# IO_Combo_WiFi.net
KiCad netlist of a schematic drawn in Altium Designer
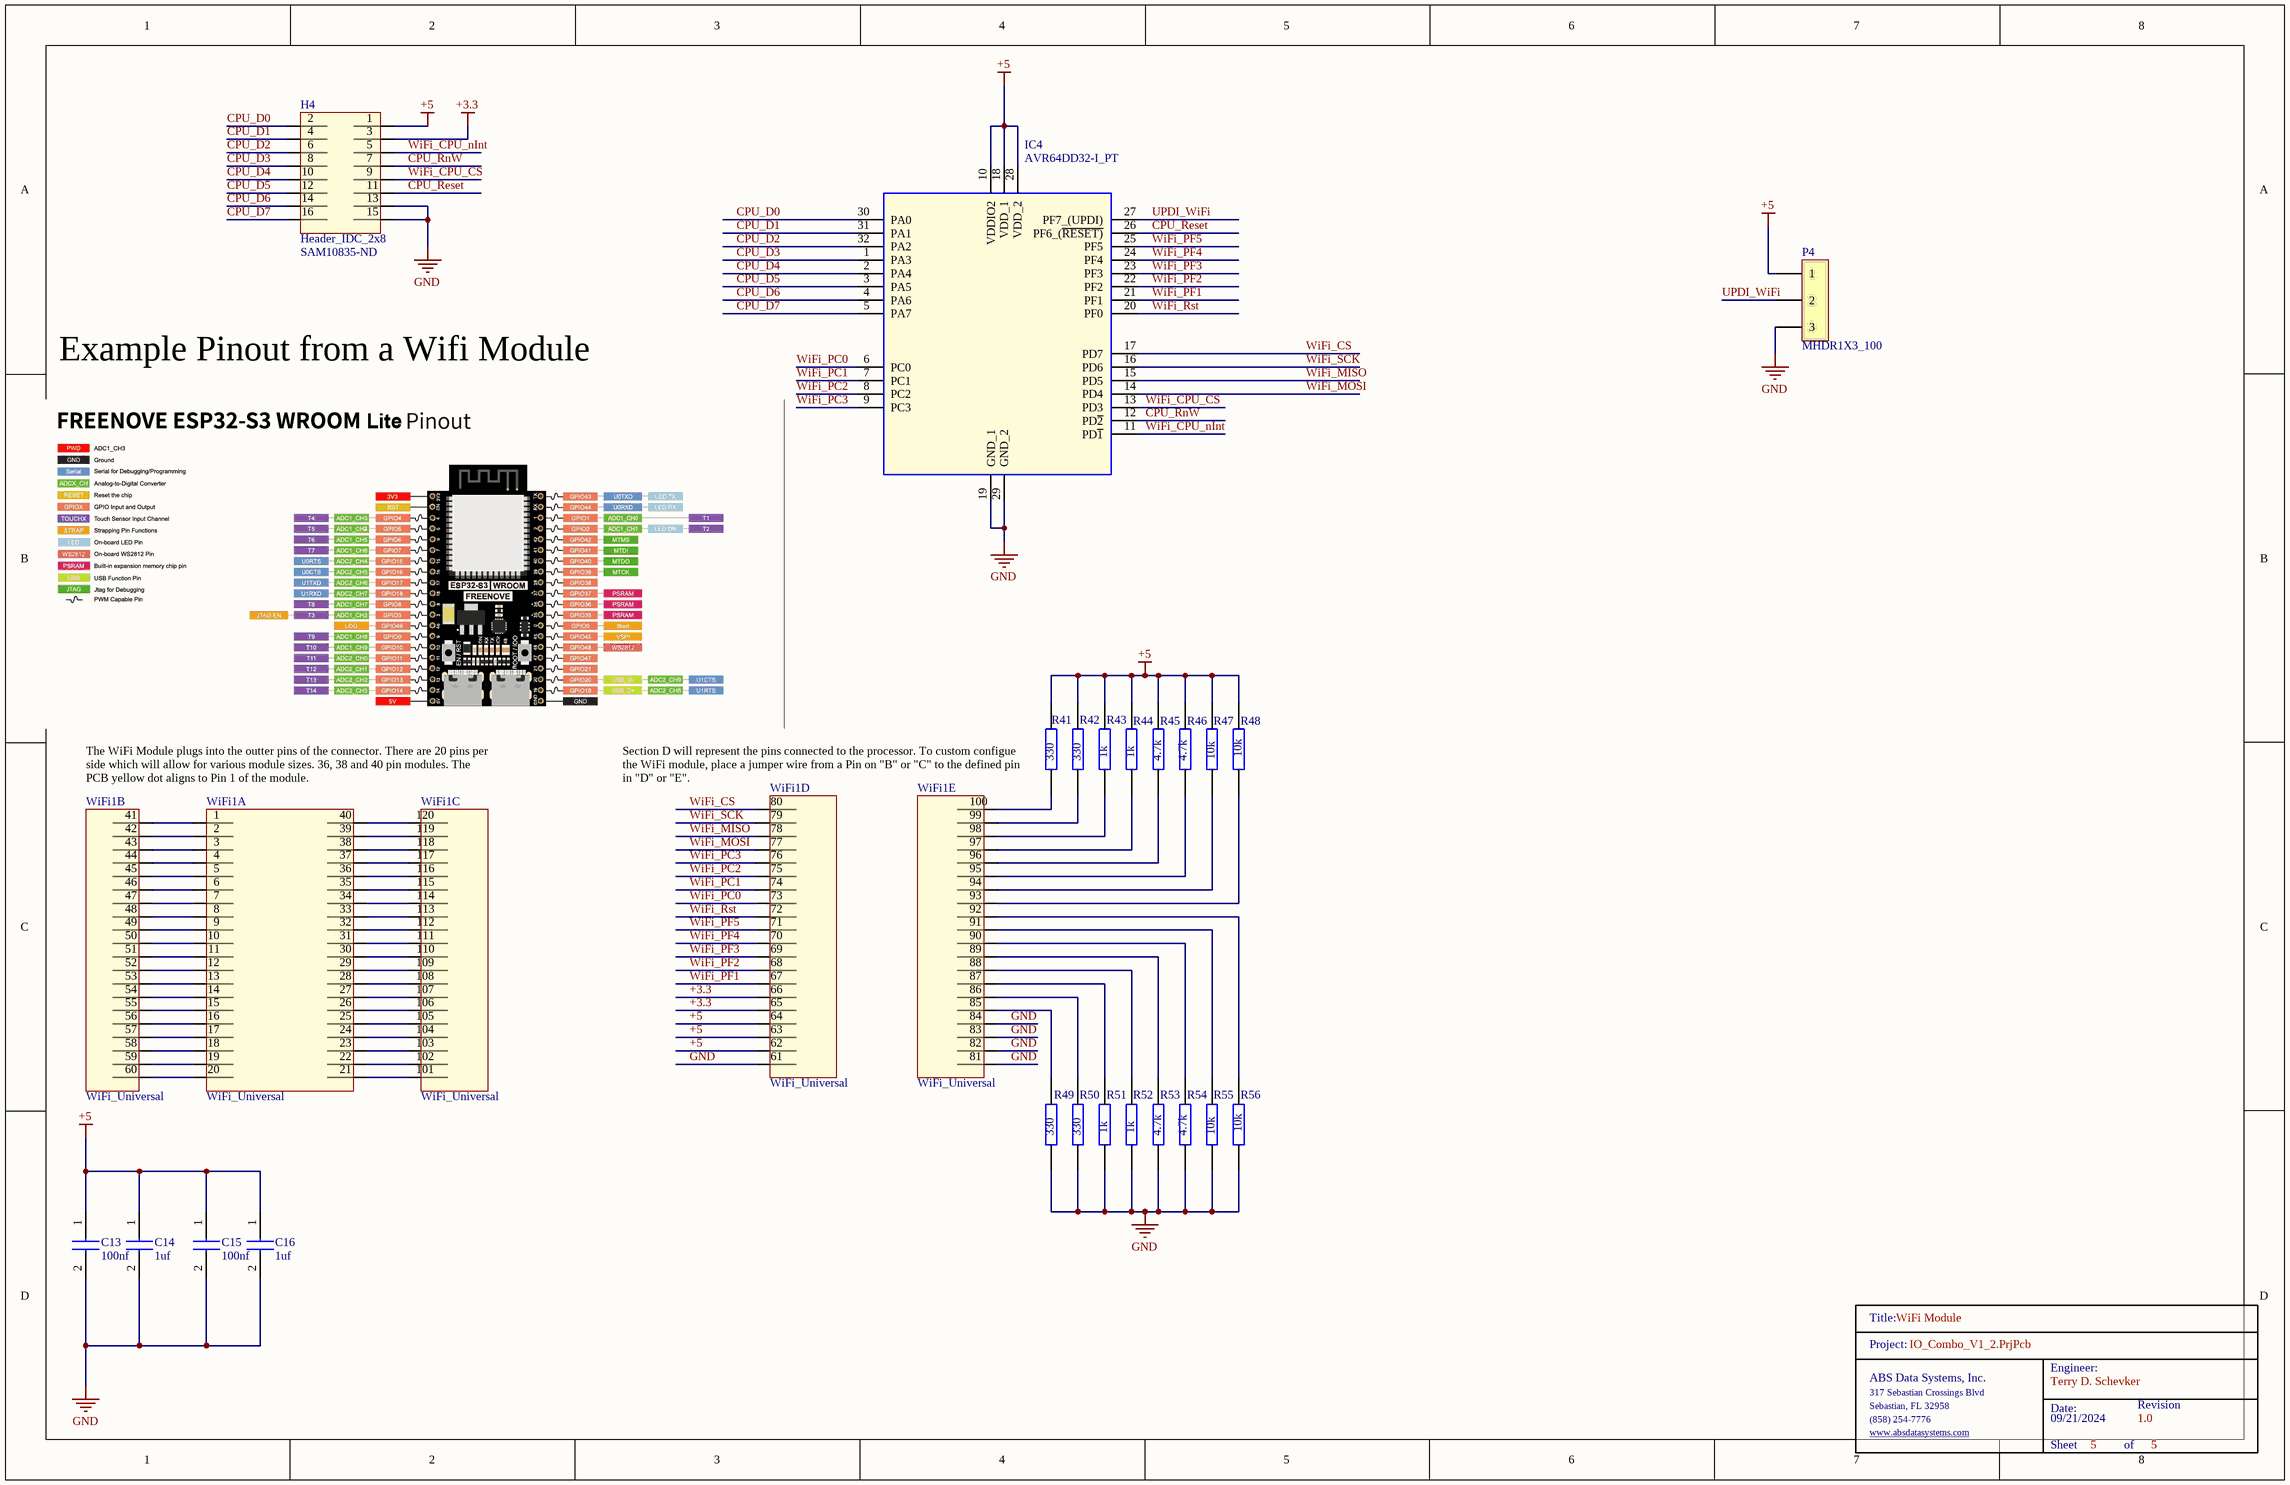
[diagram p0: IO_Combo_WiFi.SchDoc]

(export (version "E")
  (design (tool "Eeschema 10.0.6"))
  (components
    (comp (ref "C13")
      (value "100nf")
      (footprint "0603")
      (description "Samsung Electro-Mechanics 0603 100nf")
      (libsource (lib "Capacitors") (part "CL10B104JB8NNNC"))
    )
    (comp (ref "C14")
      (value "1uf")
      (footprint "0603")
      (description "Samsung Electro-Mechanics 0603 1uf")
      (libsource (lib "Capacitors") (part "CL10B105KA8NNNL"))
    )
    (comp (ref "C15")
      (value "100nf")
      (footprint "0603")
      (description "Samsung Electro-Mechanics 0603 100nf")
      (libsource (lib "Capacitors") (part "CL10B104JB8NNNC"))
    )
    (comp (ref "C16")
      (value "1uf")
      (footprint "0603")
      (description "Samsung Electro-Mechanics 0603 1uf")
      (libsource (lib "Capacitors") (part "CL10B105KA8NNNL"))
    )
    (comp (ref "H4")
      (value "Header_IDC_2x8")
      (footprint "HEADER16")
      (description "16 Pin 2x8 Through Hold IDC Connector")
      (fields
        (field (name "MANUFACTURER") "Samtec")
        (field (name "MANUFACTURER PART NUMBER") "TST-108-01-G-D")
        (field (name "SUPPLIER PART NUMBER 1") "SAM10835-ND")
      )
      (libsource (lib "Misc") (part "Header_IDC_2x8"))
    )
    (comp (ref "IC4")
      (value "AVR64DD32-I_PT")
      (footprint "CPU_Memory:QFP80P900X900X120-32N")
      (description "Integrated Circuit")
      (fields (field (name "MANUFACTURER_PART_NUMBER") "AVR64DD32-I/PT ¦ MULTI-VOLTAGE I/O"))
      (libsource (lib "CPU_Memory") (part "AVR64DD32-I_PT"))
    )
    (comp (ref "P4")
      (value "MHDR1X3_100")
      (footprint "MHDR1X3_100")
      (description "Header, 3-Pin")
      (fields (field (name "PUBLISHER") "Altium Limited"))
      (libsource (lib "Connectors") (part "MHDR1X3_100"))
    )
    (comp (ref "R41")
      (value "330")
      (footprint "0603")
      (description "YAGEO 0603 330 ohm")
      (fields
        (field (name "MOUSER PART NUMBER") "603-RC0603JR-070RL")
        (field (name "MANUFACTURER_PART_NUMBER") "RC0603JR-070RL")
      )
      (libsource (lib "Resistors") (part "AC0603FR-10330RL"))
    )
    (comp (ref "R42")
      (value "330")
      (footprint "0603")
      (description "YAGEO 0603 330 ohm")
      (fields
        (field (name "MOUSER PART NUMBER") "603-RC0603JR-070RL")
        (field (name "MANUFACTURER_PART_NUMBER") "RC0603JR-070RL")
      )
      (libsource (lib "Resistors") (part "AC0603FR-10330RL"))
    )
    (comp (ref "R43")
      (value "1k")
      (footprint "0603")
      (description "YAGEO 0603 1k ohm")
      (fields
        (field (name "MOUSER PART NUMBER") "603-RC0603JR-070RL")
        (field (name "MANUFACTURER_PART_NUMBER") "RC0603JR-070RL")
      )
      (libsource (lib "Resistors") (part "AC0603FR-7W1KL_1"))
    )
    (comp (ref "R44")
      (value "1k")
      (footprint "0603")
      (description "YAGEO 0603 1k ohm")
      (fields
        (field (name "MOUSER PART NUMBER") "603-RC0603JR-070RL")
        (field (name "MANUFACTURER_PART_NUMBER") "RC0603JR-070RL")
      )
      (libsource (lib "Resistors") (part "AC0603FR-7W1KL_1"))
    )
    (comp (ref "R45")
      (value "4.7k")
      (footprint "0603")
      (description "YAGEO 0603 4.7k")
      (fields
        (field (name "MOUSER PART NUMBER") "603-RC0603JR-070RL")
        (field (name "MANUFACTURER_PART_NUMBER") "RC0603JR-070RL")
      )
      (libsource (lib "Resistors") (part "RC0603FR-104K7L"))
    )
    (comp (ref "R46")
      (value "4.7k")
      (footprint "0603")
      (description "YAGEO 0603 4.7k")
      (fields
        (field (name "MOUSER PART NUMBER") "603-RC0603JR-070RL")
        (field (name "MANUFACTURER_PART_NUMBER") "RC0603JR-070RL")
      )
      (libsource (lib "Resistors") (part "RC0603FR-104K7L"))
    )
    (comp (ref "R47")
      (value "10k")
      (footprint "0603")
      (description "YAGEO 0603 10k ohm")
      (fields
        (field (name "MOUSER PART NUMBER") "603-RC0603JR-070RL")
        (field (name "MANUFACTURER_PART_NUMBER") "RC0603JR-070RL")
      )
      (libsource (lib "Resistors") (part "RC0603JR-0710KL"))
    )
    (comp (ref "R48")
      (value "10k")
      (footprint "0603")
      (description "YAGEO 0603 10k ohm")
      (fields
        (field (name "MOUSER PART NUMBER") "603-RC0603JR-070RL")
        (field (name "MANUFACTURER_PART_NUMBER") "RC0603JR-070RL")
      )
      (libsource (lib "Resistors") (part "RC0603JR-0710KL"))
    )
    (comp (ref "R49")
      (value "330")
      (footprint "0603")
      (description "YAGEO 0603 330 ohm")
      (fields
        (field (name "MOUSER PART NUMBER") "603-RC0603JR-070RL")
        (field (name "MANUFACTURER_PART_NUMBER") "RC0603JR-070RL")
      )
      (libsource (lib "Resistors") (part "AC0603FR-10330RL"))
    )
    (comp (ref "R50")
      (value "330")
      (footprint "0603")
      (description "YAGEO 0603 330 ohm")
      (fields
        (field (name "MOUSER PART NUMBER") "603-RC0603JR-070RL")
        (field (name "MANUFACTURER_PART_NUMBER") "RC0603JR-070RL")
      )
      (libsource (lib "Resistors") (part "AC0603FR-10330RL"))
    )
    (comp (ref "R51")
      (value "1k")
      (footprint "0603")
      (description "YAGEO 0603 1k ohm")
      (fields
        (field (name "MOUSER PART NUMBER") "603-RC0603JR-070RL")
        (field (name "MANUFACTURER_PART_NUMBER") "RC0603JR-070RL")
      )
      (libsource (lib "Resistors") (part "AC0603FR-7W1KL_1"))
    )
    (comp (ref "R52")
      (value "1k")
      (footprint "0603")
      (description "YAGEO 0603 1k ohm")
      (fields
        (field (name "MOUSER PART NUMBER") "603-RC0603JR-070RL")
        (field (name "MANUFACTURER_PART_NUMBER") "RC0603JR-070RL")
      )
      (libsource (lib "Resistors") (part "AC0603FR-7W1KL_1"))
    )
    (comp (ref "R53")
      (value "4.7k")
      (footprint "0603")
      (description "YAGEO 0603 4.7k")
      (fields
        (field (name "MOUSER PART NUMBER") "603-RC0603JR-070RL")
        (field (name "MANUFACTURER_PART_NUMBER") "RC0603JR-070RL")
      )
      (libsource (lib "Resistors") (part "RC0603FR-104K7L"))
    )
    (comp (ref "R54")
      (value "4.7k")
      (footprint "0603")
      (description "YAGEO 0603 4.7k")
      (fields
        (field (name "MOUSER PART NUMBER") "603-RC0603JR-070RL")
        (field (name "MANUFACTURER_PART_NUMBER") "RC0603JR-070RL")
      )
      (libsource (lib "Resistors") (part "RC0603FR-104K7L"))
    )
    (comp (ref "R55")
      (value "10k")
      (footprint "0603")
      (description "YAGEO 0603 10k ohm")
      (fields
        (field (name "MOUSER PART NUMBER") "603-RC0603JR-070RL")
        (field (name "MANUFACTURER_PART_NUMBER") "RC0603JR-070RL")
      )
      (libsource (lib "Resistors") (part "RC0603JR-0710KL"))
    )
    (comp (ref "R56")
      (value "10k")
      (footprint "0603")
      (description "YAGEO 0603 10k ohm")
      (fields
        (field (name "MOUSER PART NUMBER") "603-RC0603JR-070RL")
        (field (name "MANUFACTURER_PART_NUMBER") "RC0603JR-070RL")
      )
      (libsource (lib "Resistors") (part "RC0603JR-0710KL"))
    )
    (comp (ref "WiFi1")
      (value "WiFi_Universal")
      (footprint "WiFI_Universal")
      (libsource (lib "Misc") (part "WiFi_Universal"))
    )
  )
  (nets
    (net (code "1") (name "+3.3") (class "Default")
      (node (ref "H4") (pin "3") (pinfunction "3_3") (pintype "passive"))
      (node (ref "WiFi1") (pin "65") (pinfunction "65_65") (pintype "passive"))
      (node (ref "WiFi1") (pin "66") (pinfunction "66_66") (pintype "passive"))
    )
    (net (code "2") (name "+5") (class "Default")
      (node (ref "C13") (pin "1") (pinfunction "1_1") (pintype "passive"))
      (node (ref "C14") (pin "1") (pinfunction "1_1") (pintype "passive"))
      (node (ref "C15") (pin "1") (pinfunction "1_1") (pintype "passive"))
      (node (ref "C16") (pin "1") (pinfunction "1_1") (pintype "passive"))
      (node (ref "H4") (pin "1") (pinfunction "1_1") (pintype "passive"))
      (node (ref "IC4") (pin "10") (pinfunction "VDDIO2_10") (pintype "passive"))
      (node (ref "IC4") (pin "18") (pinfunction "VDD_1_18") (pintype "passive"))
      (node (ref "IC4") (pin "28") (pinfunction "VDD_2_28") (pintype "passive"))
      (node (ref "P4") (pin "1") (pinfunction "1_1") (pintype "passive"))
      (node (ref "R41") (pin "1") (pinfunction "1_1") (pintype "passive"))
      (node (ref "R42") (pin "1") (pinfunction "1_1") (pintype "passive"))
      (node (ref "R43") (pin "1") (pinfunction "1_1") (pintype "passive"))
      (node (ref "R44") (pin "1") (pinfunction "1_1") (pintype "passive"))
      (node (ref "R45") (pin "1") (pinfunction "1_1") (pintype "passive"))
      (node (ref "R46") (pin "1") (pinfunction "1_1") (pintype "passive"))
      (node (ref "R47") (pin "1") (pinfunction "1_1") (pintype "passive"))
      (node (ref "R48") (pin "1") (pinfunction "1_1") (pintype "passive"))
      (node (ref "WiFi1") (pin "62") (pinfunction "62_62") (pintype "passive"))
      (node (ref "WiFi1") (pin "63") (pinfunction "63_63") (pintype "passive"))
      (node (ref "WiFi1") (pin "64") (pinfunction "64_64") (pintype "passive"))
    )
    (net (code "3") (name "/CPU_D0") (class "Default")
      (node (ref "H4") (pin "2") (pinfunction "2_2") (pintype "passive"))
      (node (ref "IC4") (pin "30") (pinfunction "PA0_30") (pintype "passive"))
    )
    (net (code "4") (name "/CPU_D1") (class "Default")
      (node (ref "H4") (pin "4") (pinfunction "4_4") (pintype "passive"))
      (node (ref "IC4") (pin "31") (pinfunction "PA1_31") (pintype "passive"))
    )
    (net (code "5") (name "/CPU_D2") (class "Default")
      (node (ref "H4") (pin "6") (pinfunction "6_6") (pintype "passive"))
      (node (ref "IC4") (pin "32") (pinfunction "PA2_32") (pintype "passive"))
    )
    (net (code "6") (name "/CPU_D3") (class "Default")
      (node (ref "H4") (pin "8") (pinfunction "8_8") (pintype "passive"))
      (node (ref "IC4") (pin "1") (pinfunction "PA3_1") (pintype "passive"))
    )
    (net (code "7") (name "/CPU_D4") (class "Default")
      (node (ref "H4") (pin "10") (pinfunction "10_10") (pintype "passive"))
      (node (ref "IC4") (pin "2") (pinfunction "PA4_2") (pintype "passive"))
    )
    (net (code "8") (name "/CPU_D5") (class "Default")
      (node (ref "H4") (pin "12") (pinfunction "12_12") (pintype "passive"))
      (node (ref "IC4") (pin "3") (pinfunction "PA5_3") (pintype "passive"))
    )
    (net (code "9") (name "/CPU_D6") (class "Default")
      (node (ref "H4") (pin "14") (pinfunction "14_14") (pintype "passive"))
      (node (ref "IC4") (pin "4") (pinfunction "PA6_4") (pintype "passive"))
    )
    (net (code "10") (name "/CPU_D7") (class "Default")
      (node (ref "H4") (pin "16") (pinfunction "16_16") (pintype "passive"))
      (node (ref "IC4") (pin "5") (pinfunction "PA7_5") (pintype "passive"))
    )
    (net (code "11") (name "/CPU_Reset") (class "Default")
      (node (ref "H4") (pin "11") (pinfunction "11_11") (pintype "passive"))
      (node (ref "IC4") (pin "26") (pinfunction "PF6_(~{RESET)}_26") (pintype "passive"))
    )
    (net (code "12") (name "/CPU_RnW") (class "Default")
      (node (ref "H4") (pin "7") (pinfunction "7_7") (pintype "passive"))
      (node (ref "IC4") (pin "12") (pinfunction "PD~{2}_12") (pintype "passive"))
    )
    (net (code "13") (name "/UPDI_WiFi") (class "Default")
      (node (ref "IC4") (pin "27") (pinfunction "PF7_(UPDI)_27") (pintype "passive"))
      (node (ref "P4") (pin "2") (pinfunction "2_2") (pintype "passive"))
    )
    (net (code "14") (name "/WiFi_CPU_CS") (class "Default")
      (node (ref "H4") (pin "9") (pinfunction "9_9") (pintype "passive"))
      (node (ref "IC4") (pin "13") (pinfunction "PD3_13") (pintype "passive"))
    )
    (net (code "15") (name "/WiFi_CPU_nInt") (class "Default")
      (node (ref "H4") (pin "5") (pinfunction "5_5") (pintype "passive"))
      (node (ref "IC4") (pin "11") (pinfunction "PD~{1}_11") (pintype "passive"))
    )
    (net (code "16") (name "/WiFi_CS") (class "Default")
      (node (ref "IC4") (pin "17") (pinfunction "PD7_17") (pintype "passive"))
      (node (ref "WiFi1") (pin "80") (pinfunction "80_80") (pintype "passive"))
    )
    (net (code "17") (name "/WiFi_MISO") (class "Default")
      (node (ref "IC4") (pin "15") (pinfunction "PD5_15") (pintype "passive"))
      (node (ref "WiFi1") (pin "78") (pinfunction "78_78") (pintype "passive"))
    )
    (net (code "18") (name "/WiFi_MOSI") (class "Default")
      (node (ref "IC4") (pin "14") (pinfunction "PD4_14") (pintype "passive"))
      (node (ref "WiFi1") (pin "77") (pinfunction "77_77") (pintype "passive"))
    )
    (net (code "19") (name "/WiFi_PC0") (class "Default")
      (node (ref "IC4") (pin "6") (pinfunction "PC0_6") (pintype "passive"))
      (node (ref "WiFi1") (pin "73") (pinfunction "73_73") (pintype "passive"))
    )
    (net (code "20") (name "/WiFi_PC1") (class "Default")
      (node (ref "IC4") (pin "7") (pinfunction "PC1_7") (pintype "passive"))
      (node (ref "WiFi1") (pin "74") (pinfunction "74_74") (pintype "passive"))
    )
    (net (code "21") (name "/WiFi_PC2") (class "Default")
      (node (ref "IC4") (pin "8") (pinfunction "PC2_8") (pintype "passive"))
      (node (ref "WiFi1") (pin "75") (pinfunction "75_75") (pintype "passive"))
    )
    (net (code "22") (name "/WiFi_PC3") (class "Default")
      (node (ref "IC4") (pin "9") (pinfunction "PC3_9") (pintype "passive"))
      (node (ref "WiFi1") (pin "76") (pinfunction "76_76") (pintype "passive"))
    )
    (net (code "23") (name "/WiFi_PF1") (class "Default")
      (node (ref "IC4") (pin "21") (pinfunction "PF1_21") (pintype "passive"))
      (node (ref "WiFi1") (pin "67") (pinfunction "67_67") (pintype "passive"))
    )
    (net (code "24") (name "/WiFi_PF2") (class "Default")
      (node (ref "IC4") (pin "22") (pinfunction "PF2_22") (pintype "passive"))
      (node (ref "WiFi1") (pin "68") (pinfunction "68_68") (pintype "passive"))
    )
    (net (code "25") (name "/WiFi_PF3") (class "Default")
      (node (ref "IC4") (pin "23") (pinfunction "PF3_23") (pintype "passive"))
      (node (ref "WiFi1") (pin "69") (pinfunction "69_69") (pintype "passive"))
    )
    (net (code "26") (name "/WiFi_PF4") (class "Default")
      (node (ref "IC4") (pin "24") (pinfunction "PF4_24") (pintype "passive"))
      (node (ref "WiFi1") (pin "70") (pinfunction "70_70") (pintype "passive"))
    )
    (net (code "27") (name "/WiFi_PF5") (class "Default")
      (node (ref "IC4") (pin "25") (pinfunction "PF5_25") (pintype "passive"))
      (node (ref "WiFi1") (pin "71") (pinfunction "71_71") (pintype "passive"))
    )
    (net (code "28") (name "/WiFi_Rst") (class "Default")
      (node (ref "IC4") (pin "20") (pinfunction "PF0_20") (pintype "passive"))
      (node (ref "WiFi1") (pin "72") (pinfunction "72_72") (pintype "passive"))
    )
    (net (code "29") (name "/WiFi_SCK") (class "Default")
      (node (ref "IC4") (pin "16") (pinfunction "PD6_16") (pintype "passive"))
      (node (ref "WiFi1") (pin "79") (pinfunction "79_79") (pintype "passive"))
    )
    (net (code "30") (name "GND") (class "Default")
      (node (ref "C13") (pin "2") (pinfunction "2_2") (pintype "passive"))
      (node (ref "C14") (pin "2") (pinfunction "2_2") (pintype "passive"))
      (node (ref "C15") (pin "2") (pinfunction "2_2") (pintype "passive"))
      (node (ref "C16") (pin "2") (pinfunction "2_2") (pintype "passive"))
      (node (ref "H4") (pin "13") (pinfunction "13_13") (pintype "passive"))
      (node (ref "H4") (pin "15") (pinfunction "15_15") (pintype "passive"))
      (node (ref "IC4") (pin "19") (pinfunction "GND_1_19") (pintype "passive"))
      (node (ref "IC4") (pin "29") (pinfunction "GND_2_29") (pintype "passive"))
      (node (ref "P4") (pin "3") (pinfunction "3_3") (pintype "passive"))
      (node (ref "R49") (pin "2") (pinfunction "2_2") (pintype "passive"))
      (node (ref "R50") (pin "2") (pinfunction "2_2") (pintype "passive"))
      (node (ref "R51") (pin "2") (pinfunction "2_2") (pintype "passive"))
      (node (ref "R52") (pin "2") (pinfunction "2_2") (pintype "passive"))
      (node (ref "R53") (pin "2") (pinfunction "2_2") (pintype "passive"))
      (node (ref "R54") (pin "2") (pinfunction "2_2") (pintype "passive"))
      (node (ref "R55") (pin "2") (pinfunction "2_2") (pintype "passive"))
      (node (ref "R56") (pin "2") (pinfunction "2_2") (pintype "passive"))
      (node (ref "WiFi1") (pin "61") (pinfunction "61_61") (pintype "passive"))
      (node (ref "WiFi1") (pin "81") (pinfunction "81_81") (pintype "passive"))
      (node (ref "WiFi1") (pin "82") (pinfunction "82_82") (pintype "passive"))
      (node (ref "WiFi1") (pin "83") (pinfunction "83_83") (pintype "passive"))
      (node (ref "WiFi1") (pin "84") (pinfunction "84_84") (pintype "passive"))
    )
    (net (code "31") (name "Net-(R41-Pad2)") (class "Default")
      (node (ref "R41") (pin "2") (pinfunction "2_2") (pintype "passive"))
      (node (ref "WiFi1") (pin "100") (pinfunction "100_100") (pintype "passive"))
    )
    (net (code "32") (name "Net-(R42-Pad2)") (class "Default")
      (node (ref "R42") (pin "2") (pinfunction "2_2") (pintype "passive"))
      (node (ref "WiFi1") (pin "99") (pinfunction "99_99") (pintype "passive"))
    )
    (net (code "33") (name "Net-(R43-Pad2)") (class "Default")
      (node (ref "R43") (pin "2") (pinfunction "2_2") (pintype "passive"))
      (node (ref "WiFi1") (pin "98") (pinfunction "98_98") (pintype "passive"))
    )
    (net (code "34") (name "Net-(R44-Pad2)") (class "Default")
      (node (ref "R44") (pin "2") (pinfunction "2_2") (pintype "passive"))
      (node (ref "WiFi1") (pin "97") (pinfunction "97_97") (pintype "passive"))
    )
    (net (code "35") (name "Net-(R45-Pad2)") (class "Default")
      (node (ref "R45") (pin "2") (pinfunction "2_2") (pintype "passive"))
      (node (ref "WiFi1") (pin "96") (pinfunction "96_96") (pintype "passive"))
    )
    (net (code "36") (name "Net-(R46-Pad2)") (class "Default")
      (node (ref "R46") (pin "2") (pinfunction "2_2") (pintype "passive"))
      (node (ref "WiFi1") (pin "95") (pinfunction "95_95") (pintype "passive"))
    )
    (net (code "37") (name "Net-(R47-Pad2)") (class "Default")
      (node (ref "R47") (pin "2") (pinfunction "2_2") (pintype "passive"))
      (node (ref "WiFi1") (pin "94") (pinfunction "94_94") (pintype "passive"))
    )
    (net (code "38") (name "Net-(R48-Pad2)") (class "Default")
      (node (ref "R48") (pin "2") (pinfunction "2_2") (pintype "passive"))
      (node (ref "WiFi1") (pin "93") (pinfunction "93_93") (pintype "passive"))
    )
    (net (code "39") (name "Net-(R49-Pad1)") (class "Default")
      (node (ref "R49") (pin "1") (pinfunction "1_1") (pintype "passive"))
      (node (ref "WiFi1") (pin "85") (pinfunction "85_85") (pintype "passive"))
    )
    (net (code "40") (name "Net-(R50-Pad1)") (class "Default")
      (node (ref "R50") (pin "1") (pinfunction "1_1") (pintype "passive"))
      (node (ref "WiFi1") (pin "86") (pinfunction "86_86") (pintype "passive"))
    )
    (net (code "41") (name "Net-(R51-Pad1)") (class "Default")
      (node (ref "R51") (pin "1") (pinfunction "1_1") (pintype "passive"))
      (node (ref "WiFi1") (pin "87") (pinfunction "87_87") (pintype "passive"))
    )
    (net (code "42") (name "Net-(R52-Pad1)") (class "Default")
      (node (ref "R52") (pin "1") (pinfunction "1_1") (pintype "passive"))
      (node (ref "WiFi1") (pin "88") (pinfunction "88_88") (pintype "passive"))
    )
    (net (code "43") (name "Net-(R53-Pad1)") (class "Default")
      (node (ref "R53") (pin "1") (pinfunction "1_1") (pintype "passive"))
      (node (ref "WiFi1") (pin "89") (pinfunction "89_89") (pintype "passive"))
    )
    (net (code "44") (name "Net-(R54-Pad1)") (class "Default")
      (node (ref "R54") (pin "1") (pinfunction "1_1") (pintype "passive"))
      (node (ref "WiFi1") (pin "90") (pinfunction "90_90") (pintype "passive"))
    )
    (net (code "45") (name "Net-(R55-Pad1)") (class "Default")
      (node (ref "R55") (pin "1") (pinfunction "1_1") (pintype "passive"))
      (node (ref "WiFi1") (pin "91") (pinfunction "91_91") (pintype "passive"))
    )
    (net (code "46") (name "Net-(R56-Pad1)") (class "Default")
      (node (ref "R56") (pin "1") (pinfunction "1_1") (pintype "passive"))
      (node (ref "WiFi1") (pin "92") (pinfunction "92_92") (pintype "passive"))
    )
    (net (code "47") (name "Net-(WiFi1-Pad1)") (class "Default")
      (node (ref "WiFi1") (pin "1") (pinfunction "1_1") (pintype "passive"))
      (node (ref "WiFi1") (pin "41") (pinfunction "41_41") (pintype "passive"))
    )
    (net (code "48") (name "Net-(WiFi1-Pad2)") (class "Default")
      (node (ref "WiFi1") (pin "2") (pinfunction "2_2") (pintype "passive"))
      (node (ref "WiFi1") (pin "42") (pinfunction "42_42") (pintype "passive"))
    )
    (net (code "49") (name "Net-(WiFi1-Pad3)") (class "Default")
      (node (ref "WiFi1") (pin "3") (pinfunction "3_3") (pintype "passive"))
      (node (ref "WiFi1") (pin "43") (pinfunction "43_43") (pintype "passive"))
    )
    (net (code "50") (name "Net-(WiFi1-Pad4)") (class "Default")
      (node (ref "WiFi1") (pin "4") (pinfunction "4_4") (pintype "passive"))
      (node (ref "WiFi1") (pin "44") (pinfunction "44_44") (pintype "passive"))
    )
    (net (code "51") (name "Net-(WiFi1-Pad10)") (class "Default")
      (node (ref "WiFi1") (pin "10") (pinfunction "10_10") (pintype "passive"))
      (node (ref "WiFi1") (pin "50") (pinfunction "50_50") (pintype "passive"))
    )
    (net (code "52") (name "Net-(WiFi1-Pad11)") (class "Default")
      (node (ref "WiFi1") (pin "11") (pinfunction "11_11") (pintype "passive"))
      (node (ref "WiFi1") (pin "51") (pinfunction "51_51") (pintype "passive"))
    )
    (net (code "53") (name "Net-(WiFi1-Pad12)") (class "Default")
      (node (ref "WiFi1") (pin "12") (pinfunction "12_12") (pintype "passive"))
      (node (ref "WiFi1") (pin "52") (pinfunction "52_52") (pintype "passive"))
    )
    (net (code "54") (name "Net-(WiFi1-Pad13)") (class "Default")
      (node (ref "WiFi1") (pin "13") (pinfunction "13_13") (pintype "passive"))
      (node (ref "WiFi1") (pin "53") (pinfunction "53_53") (pintype "passive"))
    )
    (net (code "55") (name "Net-(WiFi1-Pad14)") (class "Default")
      (node (ref "WiFi1") (pin "14") (pinfunction "14_14") (pintype "passive"))
      (node (ref "WiFi1") (pin "54") (pinfunction "54_54") (pintype "passive"))
    )
    (net (code "56") (name "Net-(WiFi1-Pad15)") (class "Default")
      (node (ref "WiFi1") (pin "15") (pinfunction "15_15") (pintype "passive"))
      (node (ref "WiFi1") (pin "55") (pinfunction "55_55") (pintype "passive"))
    )
    (net (code "57") (name "Net-(WiFi1-Pad16)") (class "Default")
      (node (ref "WiFi1") (pin "16") (pinfunction "16_16") (pintype "passive"))
      (node (ref "WiFi1") (pin "56") (pinfunction "56_56") (pintype "passive"))
    )
    (net (code "58") (name "Net-(WiFi1-Pad17)") (class "Default")
      (node (ref "WiFi1") (pin "17") (pinfunction "17_17") (pintype "passive"))
      (node (ref "WiFi1") (pin "57") (pinfunction "57_57") (pintype "passive"))
    )
    (net (code "59") (name "Net-(WiFi1-Pad18)") (class "Default")
      (node (ref "WiFi1") (pin "18") (pinfunction "18_18") (pintype "passive"))
      (node (ref "WiFi1") (pin "58") (pinfunction "58_58") (pintype "passive"))
    )
    (net (code "60") (name "Net-(WiFi1-Pad19)") (class "Default")
      (node (ref "WiFi1") (pin "19") (pinfunction "19_19") (pintype "passive"))
      (node (ref "WiFi1") (pin "59") (pinfunction "59_59") (pintype "passive"))
    )
    (net (code "61") (name "Net-(WiFi1-Pad20)") (class "Default")
      (node (ref "WiFi1") (pin "20") (pinfunction "20_20") (pintype "passive"))
      (node (ref "WiFi1") (pin "60") (pinfunction "60_60") (pintype "passive"))
    )
    (net (code "62") (name "Net-(WiFi1-Pad45)") (class "Default")
      (node (ref "WiFi1") (pin "45") (pinfunction "45_45") (pintype "passive"))
      (node (ref "WiFi1") (pin "5") (pinfunction "5_5") (pintype "passive"))
    )
    (net (code "63") (name "Net-(WiFi1-Pad46)") (class "Default")
      (node (ref "WiFi1") (pin "46") (pinfunction "46_46") (pintype "passive"))
      (node (ref "WiFi1") (pin "6") (pinfunction "6_6") (pintype "passive"))
    )
    (net (code "64") (name "Net-(WiFi1-Pad47)") (class "Default")
      (node (ref "WiFi1") (pin "47") (pinfunction "47_47") (pintype "passive"))
      (node (ref "WiFi1") (pin "7") (pinfunction "7_7") (pintype "passive"))
    )
    (net (code "65") (name "Net-(WiFi1-Pad48)") (class "Default")
      (node (ref "WiFi1") (pin "48") (pinfunction "48_48") (pintype "passive"))
      (node (ref "WiFi1") (pin "8") (pinfunction "8_8") (pintype "passive"))
    )
    (net (code "66") (name "Net-(WiFi1-Pad49)") (class "Default")
      (node (ref "WiFi1") (pin "49") (pinfunction "49_49") (pintype "passive"))
      (node (ref "WiFi1") (pin "9") (pinfunction "9_9") (pintype "passive"))
    )
    (net (code "67") (name "Net-(WiFi1-Pad101)") (class "Default")
      (node (ref "WiFi1") (pin "101") (pinfunction "101_101") (pintype "passive"))
      (node (ref "WiFi1") (pin "21") (pinfunction "21_21") (pintype "passive"))
    )
    (net (code "68") (name "Net-(WiFi1-Pad102)") (class "Default")
      (node (ref "WiFi1") (pin "102") (pinfunction "102_102") (pintype "passive"))
      (node (ref "WiFi1") (pin "22") (pinfunction "22_22") (pintype "passive"))
    )
    (net (code "69") (name "Net-(WiFi1-Pad103)") (class "Default")
      (node (ref "WiFi1") (pin "103") (pinfunction "103_103") (pintype "passive"))
      (node (ref "WiFi1") (pin "23") (pinfunction "23_23") (pintype "passive"))
    )
    (net (code "70") (name "Net-(WiFi1-Pad104)") (class "Default")
      (node (ref "WiFi1") (pin "104") (pinfunction "104_104") (pintype "passive"))
      (node (ref "WiFi1") (pin "24") (pinfunction "24_24") (pintype "passive"))
    )
    (net (code "71") (name "Net-(WiFi1-Pad105)") (class "Default")
      (node (ref "WiFi1") (pin "105") (pinfunction "105_105") (pintype "passive"))
      (node (ref "WiFi1") (pin "25") (pinfunction "25_25") (pintype "passive"))
    )
    (net (code "72") (name "Net-(WiFi1-Pad106)") (class "Default")
      (node (ref "WiFi1") (pin "106") (pinfunction "106_106") (pintype "passive"))
      (node (ref "WiFi1") (pin "26") (pinfunction "26_26") (pintype "passive"))
    )
    (net (code "73") (name "Net-(WiFi1-Pad107)") (class "Default")
      (node (ref "WiFi1") (pin "107") (pinfunction "107_107") (pintype "passive"))
      (node (ref "WiFi1") (pin "27") (pinfunction "27_27") (pintype "passive"))
    )
    (net (code "74") (name "Net-(WiFi1-Pad108)") (class "Default")
      (node (ref "WiFi1") (pin "108") (pinfunction "108_108") (pintype "passive"))
      (node (ref "WiFi1") (pin "28") (pinfunction "28_28") (pintype "passive"))
    )
    (net (code "75") (name "Net-(WiFi1-Pad109)") (class "Default")
      (node (ref "WiFi1") (pin "109") (pinfunction "109_109") (pintype "passive"))
      (node (ref "WiFi1") (pin "29") (pinfunction "29_29") (pintype "passive"))
    )
    (net (code "76") (name "Net-(WiFi1-Pad110)") (class "Default")
      (node (ref "WiFi1") (pin "110") (pinfunction "110_110") (pintype "passive"))
      (node (ref "WiFi1") (pin "30") (pinfunction "30_30") (pintype "passive"))
    )
    (net (code "77") (name "Net-(WiFi1-Pad111)") (class "Default")
      (node (ref "WiFi1") (pin "111") (pinfunction "111_111") (pintype "passive"))
      (node (ref "WiFi1") (pin "31") (pinfunction "31_31") (pintype "passive"))
    )
    (net (code "78") (name "Net-(WiFi1-Pad112)") (class "Default")
      (node (ref "WiFi1") (pin "112") (pinfunction "112_112") (pintype "passive"))
      (node (ref "WiFi1") (pin "32") (pinfunction "32_32") (pintype "passive"))
    )
    (net (code "79") (name "Net-(WiFi1-Pad113)") (class "Default")
      (node (ref "WiFi1") (pin "113") (pinfunction "113_113") (pintype "passive"))
      (node (ref "WiFi1") (pin "33") (pinfunction "33_33") (pintype "passive"))
    )
    (net (code "80") (name "Net-(WiFi1-Pad114)") (class "Default")
      (node (ref "WiFi1") (pin "114") (pinfunction "114_114") (pintype "passive"))
      (node (ref "WiFi1") (pin "34") (pinfunction "34_34") (pintype "passive"))
    )
    (net (code "81") (name "Net-(WiFi1-Pad115)") (class "Default")
      (node (ref "WiFi1") (pin "115") (pinfunction "115_115") (pintype "passive"))
      (node (ref "WiFi1") (pin "35") (pinfunction "35_35") (pintype "passive"))
    )
    (net (code "82") (name "Net-(WiFi1-Pad116)") (class "Default")
      (node (ref "WiFi1") (pin "116") (pinfunction "116_116") (pintype "passive"))
      (node (ref "WiFi1") (pin "36") (pinfunction "36_36") (pintype "passive"))
    )
    (net (code "83") (name "Net-(WiFi1-Pad117)") (class "Default")
      (node (ref "WiFi1") (pin "117") (pinfunction "117_117") (pintype "passive"))
      (node (ref "WiFi1") (pin "37") (pinfunction "37_37") (pintype "passive"))
    )
    (net (code "84") (name "Net-(WiFi1-Pad118)") (class "Default")
      (node (ref "WiFi1") (pin "118") (pinfunction "118_118") (pintype "passive"))
      (node (ref "WiFi1") (pin "38") (pinfunction "38_38") (pintype "passive"))
    )
    (net (code "85") (name "Net-(WiFi1-Pad119)") (class "Default")
      (node (ref "WiFi1") (pin "119") (pinfunction "119_119") (pintype "passive"))
      (node (ref "WiFi1") (pin "39") (pinfunction "39_39") (pintype "passive"))
    )
    (net (code "86") (name "Net-(WiFi1-Pad120)") (class "Default")
      (node (ref "WiFi1") (pin "120") (pinfunction "120_120") (pintype "passive"))
      (node (ref "WiFi1") (pin "40") (pinfunction "40_40") (pintype "passive"))
    )
  )
)
